# I2C-LTS-LC.net
KiCad netlist of a schematic drawn in EAGLE
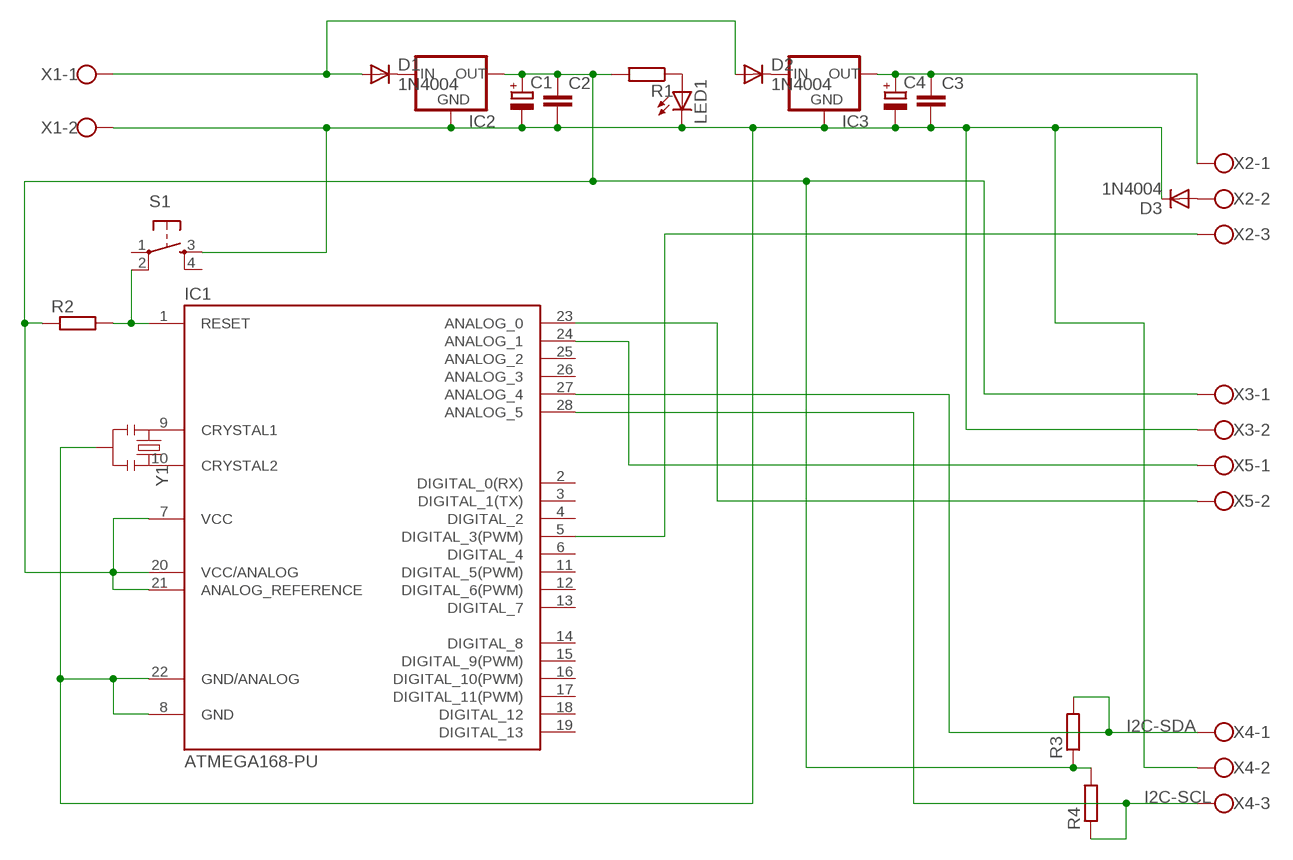
[diagram p0: schematic, sheet 1]

(export (version "E")
  (design (tool "Eeschema 10.0.6"))
  (components
    (comp (ref "C1")
      (value "CPOL-EUE5-10.5")
      (footprint "eagle-import:E5-10,5")
      (libsource (lib "eagle-import") (part "CPOL-EUE5-10.5"))
    )
    (comp (ref "C2")
      (value "C-EU050-024X044")
      (footprint "eagle-import:C050-024X044")
      (libsource (lib "eagle-import") (part "C-EU050-024X044"))
    )
    (comp (ref "C3")
      (value "C-EU050-024X044")
      (footprint "eagle-import:C050-024X044")
      (libsource (lib "eagle-import") (part "C-EU050-024X044"))
    )
    (comp (ref "C4")
      (value "CPOL-EUE5-10.5")
      (footprint "eagle-import:E5-10,5")
      (libsource (lib "eagle-import") (part "CPOL-EUE5-10.5"))
    )
    (comp (ref "D1")
      (value "1N4004")
      (footprint "eagle-import:DO41-10")
      (libsource (lib "eagle-import") (part "1N4004"))
    )
    (comp (ref "D2")
      (value "1N4004")
      (footprint "eagle-import:DO41-10")
      (libsource (lib "eagle-import") (part "1N4004"))
    )
    (comp (ref "D3")
      (value "1N4004")
      (footprint "eagle-import:DO41-10")
      (libsource (lib "eagle-import") (part "1N4004"))
    )
    (comp (ref "IC1")
      (value "ATMEGA168-PU")
      (footprint "eagle-import:DIL28-3")
      (libsource (lib "eagle-import") (part "ATMEGA168-PU"))
    )
    (comp (ref "IC2")
      (value "78XXL")
      (footprint "eagle-import:78XXL")
      (libsource (lib "eagle-import") (part "78XXL"))
    )
    (comp (ref "IC3")
      (value "78XXL")
      (footprint "eagle-import:78XXL")
      (libsource (lib "eagle-import") (part "78XXL"))
    )
    (comp (ref "LED1")
      (value "LED3MM")
      (footprint "eagle-import:LED3MM")
      (libsource (lib "eagle-import") (part "LED3MM"))
    )
    (comp (ref "R1")
      (value "R-EU_0207/12")
      (footprint "eagle-import:0207_12")
      (libsource (lib "eagle-import") (part "R-EU_0207/12"))
    )
    (comp (ref "R2")
      (value "R-EU_0207/12")
      (footprint "eagle-import:0207_12")
      (libsource (lib "eagle-import") (part "R-EU_0207/12"))
    )
    (comp (ref "R3")
      (value "R-EU_0207/12")
      (footprint "eagle-import:0207_12")
      (libsource (lib "eagle-import") (part "R-EU_0207/12"))
    )
    (comp (ref "R4")
      (value "R-EU_0207/12")
      (footprint "eagle-import:0207_12")
      (libsource (lib "eagle-import") (part "R-EU_0207/12"))
    )
    (comp (ref "S1")
      (value "TAC_SWITCHPTH")
      (footprint "eagle-import:TACTILE-PTH")
      (libsource (lib "eagle-import") (part "TAC_SWITCHPTH"))
    )
    (comp (ref "X1")
      (value "W237-102")
      (footprint "eagle-import:W237-102")
      (fields (field (name "MPN") "237-102"))
      (libsource (lib "eagle-import") (part "W237-102"))
    )
    (comp (ref "X2")
      (value "W237-103")
      (footprint "eagle-import:W237-103")
      (fields (field (name "MPN") "237-103"))
      (libsource (lib "eagle-import") (part "W237-103"))
    )
    (comp (ref "X3")
      (value "W237-102")
      (footprint "eagle-import:W237-102")
      (fields (field (name "MPN") "237-102"))
      (libsource (lib "eagle-import") (part "W237-102"))
    )
    (comp (ref "X4")
      (value "W237-103")
      (footprint "eagle-import:W237-103")
      (fields (field (name "MPN") "237-103"))
      (libsource (lib "eagle-import") (part "W237-103"))
    )
    (comp (ref "X5")
      (value "W237-102")
      (footprint "eagle-import:W237-102")
      (fields (field (name "MPN") "237-102"))
      (libsource (lib "eagle-import") (part "W237-102"))
    )
    (comp (ref "Y1")
      (value "RESONATORPTH")
      (footprint "eagle-import:RESONATOR-PTH")
      (libsource (lib "eagle-import") (part "RESONATORPTH"))
    )
  )
  (nets
    (net (code "1") (name "/I2C-SCL") (class "Default")
      (node (ref "IC1") (pin "28") (pinfunction "ANALOG_5_28") (pintype "bidirectional"))
      (node (ref "R4") (pin "1") (pinfunction "1_1") (pintype "passive"))
      (node (ref "X4") (pin "3") (pinfunction "KL_3") (pintype "passive"))
    )
    (net (code "2") (name "/I2C-SDA") (class "Default")
      (node (ref "IC1") (pin "27") (pinfunction "ANALOG_4_27") (pintype "bidirectional"))
      (node (ref "R3") (pin "2") (pinfunction "2_2") (pintype "passive"))
      (node (ref "X4") (pin "1") (pinfunction "KL_1") (pintype "passive"))
    )
    (net (code "3") (name "Net-(D1-PadC)") (class "Default")
      (node (ref "D1") (pin "C") (pinfunction "C_C") (pintype "passive"))
      (node (ref "IC2") (pin "IN") (pinfunction "IN_IN") (pintype "input"))
    )
    (net (code "4") (name "Net-(D2-PadC)") (class "Default")
      (node (ref "D2") (pin "C") (pinfunction "C_C") (pintype "passive"))
      (node (ref "IC3") (pin "IN") (pinfunction "IN_IN") (pintype "input"))
    )
    (net (code "5") (name "Net-(IC1-ANALOG_0)") (class "Default")
      (node (ref "IC1") (pin "23") (pinfunction "ANALOG_0_23") (pintype "bidirectional"))
      (node (ref "X5") (pin "2") (pinfunction "KL_2") (pintype "passive"))
    )
    (net (code "6") (name "Net-(IC1-ANALOG_1)") (class "Default")
      (node (ref "IC1") (pin "24") (pinfunction "ANALOG_1_24") (pintype "bidirectional"))
      (node (ref "X5") (pin "1") (pinfunction "KL_1") (pintype "passive"))
    )
    (net (code "7") (name "Net-(IC1-ANALOG_REFERENCE)") (class "Default")
      (node (ref "C1") (pin "+") (pinfunction "+_+") (pintype "passive"))
      (node (ref "C2") (pin "1") (pinfunction "1_1") (pintype "passive"))
      (node (ref "IC1") (pin "20") (pinfunction "VCC/ANALOG_20") (pintype "passive"))
      (node (ref "IC1") (pin "21") (pinfunction "ANALOG_REFERENCE_21") (pintype "passive"))
      (node (ref "IC1") (pin "7") (pinfunction "VCC_7") (pintype "power_in"))
      (node (ref "IC2") (pin "OUT") (pinfunction "OUT_OUT") (pintype "passive"))
      (node (ref "R1") (pin "2") (pinfunction "2_2") (pintype "passive"))
      (node (ref "R2") (pin "1") (pinfunction "1_1") (pintype "passive"))
      (node (ref "R3") (pin "1") (pinfunction "1_1") (pintype "passive"))
      (node (ref "R4") (pin "2") (pinfunction "2_2") (pintype "passive"))
      (node (ref "X3") (pin "1") (pinfunction "KL_1") (pintype "passive"))
    )
    (net (code "8") (name "Net-(IC1-CRYSTAL1)") (class "Default")
      (node (ref "IC1") (pin "9") (pinfunction "CRYSTAL1_9") (pintype "bidirectional"))
      (node (ref "Y1") (pin "1") (pinfunction "1_1") (pintype "passive"))
    )
    (net (code "9") (name "Net-(IC1-CRYSTAL2)") (class "Default")
      (node (ref "IC1") (pin "10") (pinfunction "CRYSTAL2_10") (pintype "bidirectional"))
      (node (ref "Y1") (pin "3") (pinfunction "3_3") (pintype "passive"))
    )
    (net (code "10") (name "Net-(IC1-DIGITAL_3(PWM))") (class "Default")
      (node (ref "IC1") (pin "5") (pinfunction "DIGITAL_3(PWM)_5") (pintype "bidirectional"))
      (node (ref "X2") (pin "3") (pinfunction "KL_3") (pintype "passive"))
    )
    (net (code "11") (name "Net-(IC1-GND)") (class "Default")
      (node (ref "C1") (pin "-") (pinfunction "-_-") (pintype "passive"))
      (node (ref "C2") (pin "2") (pinfunction "2_2") (pintype "passive"))
      (node (ref "C3") (pin "2") (pinfunction "2_2") (pintype "passive"))
      (node (ref "C4") (pin "-") (pinfunction "-_-") (pintype "passive"))
      (node (ref "D3") (pin "C") (pinfunction "C_C") (pintype "passive"))
      (node (ref "IC1") (pin "22") (pinfunction "GND/ANALOG_22") (pintype "power_in"))
      (node (ref "IC1") (pin "8") (pinfunction "GND_8") (pintype "power_in"))
      (node (ref "IC2") (pin "GND") (pinfunction "GND_GND") (pintype "input"))
      (node (ref "IC3") (pin "GND") (pinfunction "GND_GND") (pintype "input"))
      (node (ref "LED1") (pin "K") (pinfunction "C_K") (pintype "passive"))
      (node (ref "S1") (pin "3") (pinfunction "3_3") (pintype "passive"))
      (node (ref "X1") (pin "2") (pinfunction "KL_2") (pintype "passive"))
      (node (ref "X3") (pin "2") (pinfunction "KL_2") (pintype "passive"))
      (node (ref "X4") (pin "2") (pinfunction "KL_2") (pintype "passive"))
      (node (ref "Y1") (pin "2") (pinfunction "2_2") (pintype "passive"))
    )
    (net (code "12") (name "Net-(IC1-RESET)") (class "Default")
      (node (ref "IC1") (pin "1") (pinfunction "RESET_1") (pintype "bidirectional"))
      (node (ref "R2") (pin "2") (pinfunction "2_2") (pintype "passive"))
      (node (ref "S1") (pin "2") (pinfunction "2_2") (pintype "passive"))
    )
    (net (code "13") (name "Net-(LED1-PadA)") (class "Default")
      (node (ref "LED1") (pin "A") (pinfunction "A_A") (pintype "passive"))
      (node (ref "R1") (pin "1") (pinfunction "1_1") (pintype "passive"))
    )
    (net (code "14") (name "Net-(X1A-KL)") (class "Default")
      (node (ref "D1") (pin "A") (pinfunction "A_A") (pintype "passive"))
      (node (ref "D2") (pin "A") (pinfunction "A_A") (pintype "passive"))
      (node (ref "X1") (pin "1") (pinfunction "KL_1") (pintype "passive"))
    )
    (net (code "15") (name "Net-(X2A-KL)") (class "Default")
      (node (ref "C3") (pin "1") (pinfunction "1_1") (pintype "passive"))
      (node (ref "C4") (pin "+") (pinfunction "+_+") (pintype "passive"))
      (node (ref "IC3") (pin "OUT") (pinfunction "OUT_OUT") (pintype "passive"))
      (node (ref "X2") (pin "1") (pinfunction "KL_1") (pintype "passive"))
    )
    (net (code "16") (name "Net-(X2B-KL)") (class "Default")
      (node (ref "D3") (pin "A") (pinfunction "A_A") (pintype "passive"))
      (node (ref "X2") (pin "2") (pinfunction "KL_2") (pintype "passive"))
    )
    (net (code "17") (name "unconnected-(IC1-ANALOG_2-Pad25)") (class "Default")
      (node (ref "IC1") (pin "25") (pinfunction "ANALOG_2_25") (pintype "bidirectional"))
    )
    (net (code "18") (name "unconnected-(IC1-ANALOG_3-Pad26)") (class "Default")
      (node (ref "IC1") (pin "26") (pinfunction "ANALOG_3_26") (pintype "bidirectional"))
    )
    (net (code "19") (name "unconnected-(IC1-DIGITAL_0(RX)-Pad2)") (class "Default")
      (node (ref "IC1") (pin "2") (pinfunction "DIGITAL_0(RX)_2") (pintype "bidirectional"))
    )
    (net (code "20") (name "unconnected-(IC1-DIGITAL_1(TX)-Pad3)") (class "Default")
      (node (ref "IC1") (pin "3") (pinfunction "DIGITAL_1(TX)_3") (pintype "bidirectional"))
    )
    (net (code "21") (name "unconnected-(IC1-DIGITAL_2-Pad4)") (class "Default")
      (node (ref "IC1") (pin "4") (pinfunction "DIGITAL_2_4") (pintype "bidirectional"))
    )
    (net (code "22") (name "unconnected-(IC1-DIGITAL_4-Pad6)") (class "Default")
      (node (ref "IC1") (pin "6") (pinfunction "DIGITAL_4_6") (pintype "bidirectional"))
    )
    (net (code "23") (name "unconnected-(IC1-DIGITAL_5(PWM)-Pad11)") (class "Default")
      (node (ref "IC1") (pin "11") (pinfunction "DIGITAL_5(PWM)_11") (pintype "bidirectional"))
    )
    (net (code "24") (name "unconnected-(IC1-DIGITAL_6(PWM)-Pad12)") (class "Default")
      (node (ref "IC1") (pin "12") (pinfunction "DIGITAL_6(PWM)_12") (pintype "bidirectional"))
    )
    (net (code "25") (name "unconnected-(IC1-DIGITAL_7-Pad13)") (class "Default")
      (node (ref "IC1") (pin "13") (pinfunction "DIGITAL_7_13") (pintype "bidirectional"))
    )
    (net (code "26") (name "unconnected-(IC1-DIGITAL_8-Pad14)") (class "Default")
      (node (ref "IC1") (pin "14") (pinfunction "DIGITAL_8_14") (pintype "bidirectional"))
    )
    (net (code "27") (name "unconnected-(IC1-DIGITAL_9(PWM)-Pad15)") (class "Default")
      (node (ref "IC1") (pin "15") (pinfunction "DIGITAL_9(PWM)_15") (pintype "bidirectional"))
    )
    (net (code "28") (name "unconnected-(IC1-DIGITAL_10(PWM)-Pad16)") (class "Default")
      (node (ref "IC1") (pin "16") (pinfunction "DIGITAL_10(PWM)_16") (pintype "bidirectional"))
    )
    (net (code "29") (name "unconnected-(IC1-DIGITAL_11(PWM)-Pad17)") (class "Default")
      (node (ref "IC1") (pin "17") (pinfunction "DIGITAL_11(PWM)_17") (pintype "bidirectional"))
    )
    (net (code "30") (name "unconnected-(IC1-DIGITAL_12-Pad18)") (class "Default")
      (node (ref "IC1") (pin "18") (pinfunction "DIGITAL_12_18") (pintype "bidirectional"))
    )
    (net (code "31") (name "unconnected-(IC1-DIGITAL_13-Pad19)") (class "Default")
      (node (ref "IC1") (pin "19") (pinfunction "DIGITAL_13_19") (pintype "bidirectional"))
    )
    (net (code "32") (name "unconnected-(S1-Pad1)") (class "Default")
      (node (ref "S1") (pin "1") (pinfunction "1_1") (pintype "passive"))
    )
    (net (code "33") (name "unconnected-(S1-Pad4)") (class "Default")
      (node (ref "S1") (pin "4") (pinfunction "4_4") (pintype "passive"))
    )
  )
)
